# USB.net
KiCad netlist of a schematic drawn in Altium Designer
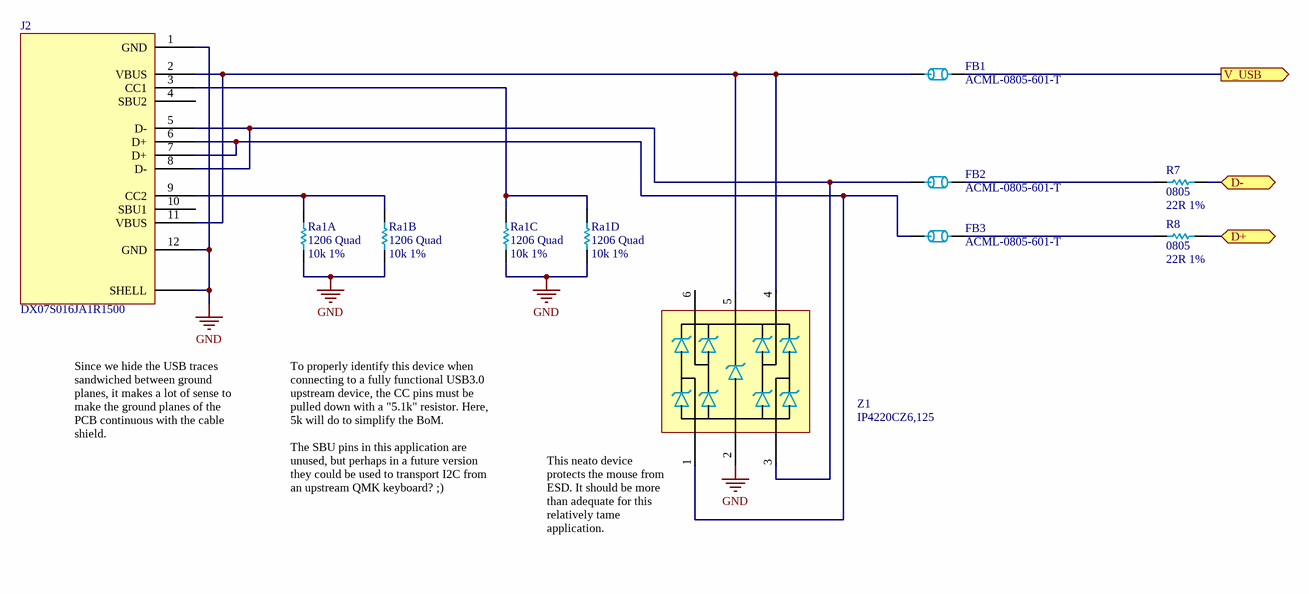
[diagram p0: USB.SchDoc]

(export (version "E")
  (design (tool "Eeschema 10.0.6"))
  (components
    (comp (ref "FB1")
      (value "ACML-0805-601-T")
      (footprint "0805")
      (description "FERRITE BEAD 600 OHM 0805 1LN")
      (libsource (lib "Chip_Passives") (part "ACML-0805-601-T"))
    )
    (comp (ref "FB2")
      (value "ACML-0805-601-T")
      (footprint "0805")
      (description "FERRITE BEAD 600 OHM 0805 1LN")
      (libsource (lib "Chip_Passives") (part "ACML-0805-601-T"))
    )
    (comp (ref "FB3")
      (value "ACML-0805-601-T")
      (footprint "0805")
      (description "FERRITE BEAD 600 OHM 0805 1LN")
      (libsource (lib "Chip_Passives") (part "ACML-0805-601-T"))
    )
    (comp (ref "J2")
      (value "DX07S016JA1R1500")
      (footprint "DX07S016JA1R1500")
      (libsource (lib "Connectors") (part "DX07S016JA1R1500"))
    )
    (comp (ref "R7")
      (value "0805")
      (footprint "0805")
      (description "Chip resistor")
      (fields (field (name "ALTIUM_VALUE") "22R 1%"))
      (libsource (lib "Chip_Passives") (part "Res 22R 1% 0805"))
    )
    (comp (ref "R8")
      (value "0805")
      (footprint "0805")
      (description "Chip resistor")
      (fields (field (name "ALTIUM_VALUE") "22R 1%"))
      (libsource (lib "Chip_Passives") (part "Res 22R 1% 0805"))
    )
    (comp (ref "Ra1")
      (value "1206 Quad")
      (footprint "4x 10k 1% - CAC-80P320X160-8M")
      (description "Chip resistor")
      (fields (field (name "ALTIUM_VALUE") "10k 1%"))
      (libsource (lib "Chip_Passives") (part "Quad Res 10k 1% 1206"))
    )
    (comp (ref "Z1")
      (value "IP4220CZ6,125")
      (footprint "PESD3V3S4UD - SOT95P275X110-6N")
      (description "TVS DIODE 5.5V 6TSOP (Low capacitance, USB)")
      (libsource (lib "Diodes") (part "IP4220CZ6,125"))
    )
  )
  (nets
    (net (code "1") (name "/D+") (class "Default")
      (node (ref "R8") (pin "2") (pinfunction "2_2") (pintype "passive"))
    )
    (net (code "2") (name "/D-") (class "Default")
      (node (ref "R7") (pin "2") (pinfunction "2_2") (pintype "passive"))
    )
    (net (code "3") (name "/V_USB") (class "Default")
      (node (ref "FB1") (pin "2") (pinfunction "2_2") (pintype "passive"))
    )
    (net (code "4") (name "GND") (class "Default")
      (node (ref "J2") (pin "1") (pinfunction "GND_1") (pintype "passive"))
      (node (ref "J2") (pin "12") (pinfunction "GND_12") (pintype "passive"))
      (node (ref "J2") (pin "SHELL") (pinfunction "SHELL_SHELL") (pintype "passive"))
      (node (ref "Ra1") (pin "1") (pinfunction "1_1") (pintype "passive"))
      (node (ref "Ra1") (pin "2") (pinfunction "2_2") (pintype "passive"))
      (node (ref "Ra1") (pin "3") (pinfunction "3_3") (pintype "passive"))
      (node (ref "Ra1") (pin "4") (pinfunction "4_4") (pintype "passive"))
      (node (ref "Z1") (pin "2") (pinfunction "2_2") (pintype "passive"))
    )
    (net (code "5") (name "Net-(FB1-Pad1)") (class "Default")
      (node (ref "FB1") (pin "1") (pinfunction "1_1") (pintype "passive"))
      (node (ref "J2") (pin "11") (pinfunction "VBUS_11") (pintype "passive"))
      (node (ref "J2") (pin "2") (pinfunction "VBUS_2") (pintype "passive"))
      (node (ref "Z1") (pin "4") (pinfunction "4_4") (pintype "passive"))
      (node (ref "Z1") (pin "5") (pinfunction "5_5") (pintype "passive"))
    )
    (net (code "6") (name "Net-(FB2-Pad1)") (class "Default")
      (node (ref "FB2") (pin "1") (pinfunction "1_1") (pintype "passive"))
      (node (ref "J2") (pin "5") (pinfunction "D-_5") (pintype "passive"))
      (node (ref "J2") (pin "8") (pinfunction "D-_8") (pintype "passive"))
      (node (ref "Z1") (pin "3") (pinfunction "3_3") (pintype "passive"))
    )
    (net (code "7") (name "Net-(FB2-Pad2)") (class "Default")
      (node (ref "FB2") (pin "2") (pinfunction "2_2") (pintype "passive"))
      (node (ref "R7") (pin "1") (pinfunction "1_1") (pintype "passive"))
    )
    (net (code "8") (name "Net-(FB3-Pad1)") (class "Default")
      (node (ref "FB3") (pin "1") (pinfunction "1_1") (pintype "passive"))
      (node (ref "J2") (pin "6") (pinfunction "D+_6") (pintype "passive"))
      (node (ref "J2") (pin "7") (pinfunction "D+_7") (pintype "passive"))
      (node (ref "Z1") (pin "1") (pinfunction "1_1") (pintype "passive"))
    )
    (net (code "9") (name "Net-(FB3-Pad2)") (class "Default")
      (node (ref "FB3") (pin "2") (pinfunction "2_2") (pintype "passive"))
      (node (ref "R8") (pin "1") (pinfunction "1_1") (pintype "passive"))
    )
    (net (code "10") (name "Net-(J2-CC1)") (class "Default")
      (node (ref "J2") (pin "3") (pinfunction "CC1_3") (pintype "passive"))
      (node (ref "Ra1") (pin "5") (pinfunction "5_5") (pintype "passive"))
      (node (ref "Ra1") (pin "6") (pinfunction "6_6") (pintype "passive"))
    )
    (net (code "11") (name "Net-(J2-CC2)") (class "Default")
      (node (ref "J2") (pin "9") (pinfunction "CC2_9") (pintype "passive"))
      (node (ref "Ra1") (pin "7") (pinfunction "7_7") (pintype "passive"))
      (node (ref "Ra1") (pin "8") (pinfunction "8_8") (pintype "passive"))
    )
    (net (code "12") (name "unconnected-(J2-SBU1-Pad10)") (class "Default")
      (node (ref "J2") (pin "10") (pinfunction "SBU1_10") (pintype "passive"))
    )
    (net (code "13") (name "unconnected-(J2-SBU2-Pad4)") (class "Default")
      (node (ref "J2") (pin "4") (pinfunction "SBU2_4") (pintype "passive"))
    )
    (net (code "14") (name "unconnected-(Z1-Pad6)") (class "Default")
      (node (ref "Z1") (pin "6") (pinfunction "6_6") (pintype "passive"))
    )
  )
)
